# STM32.net
KiCad netlist of a schematic drawn in Altium Designer
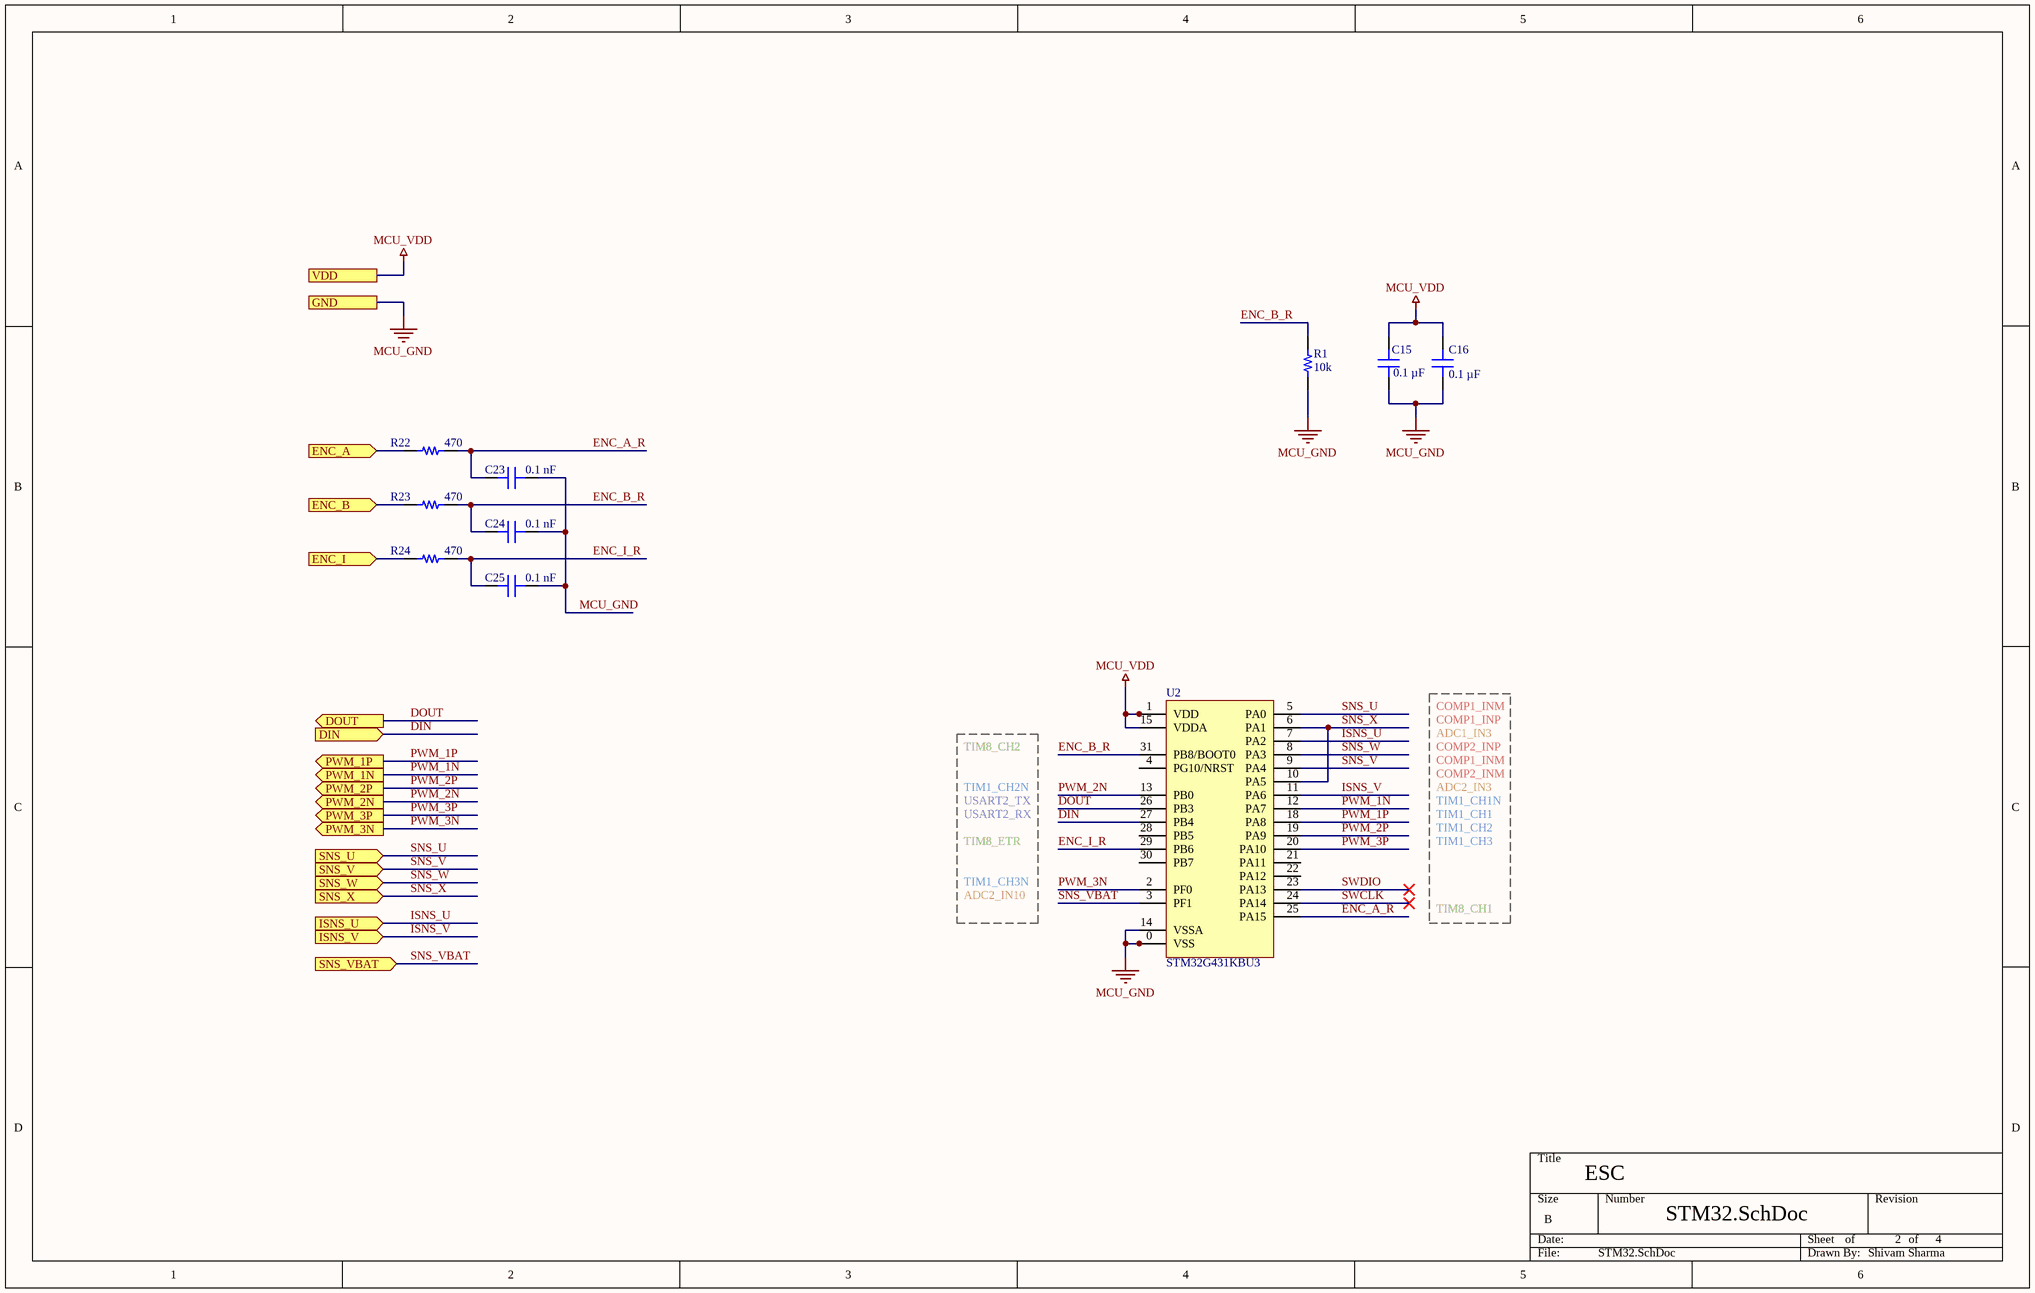
[diagram p0: STM32.SchDoc]

(export (version "E")
  (design (tool "Eeschema 10.0.6"))
  (components
    (comp (ref "C15")
      (value "0.1 µF")
      (footprint "CAP 0402_1005")
      (description "CAP CER 0.1UF 16V X7R 0402")
      (fields (field (name "PART NUMBER") "C0402C104K4RACAUTO") (field (name "MANUFACTURER") "KEMET"))
      (libsource (lib "Celestial Altium Library - altium_library") (part "Capacitor"))
    )
    (comp (ref "C16")
      (value "0.1 µF")
      (footprint "CAP 0402_1005")
      (description "CAP CER 0.1UF 16V X7R 0402")
      (fields (field (name "PART NUMBER") "C0402C104K4RACAUTO") (field (name "MANUFACTURER") "KEMET"))
      (libsource (lib "Celestial Altium Library - altium_library") (part "Capacitor"))
    )
    (comp (ref "C23")
      (value "0.1 nF")
      (footprint "CAP 0402_1005")
      (description "CAP CER 0.1UF 16V X7R 0402")
      (fields (field (name "PART NUMBER") "C0402C104K4RACAUTO") (field (name "MANUFACTURER") "KEMET"))
      (libsource (lib "Celestial Altium Library - altium_library") (part "Capacitor"))
    )
    (comp (ref "C24")
      (value "0.1 nF")
      (footprint "CAP 0402_1005")
      (description "CAP CER 0.1UF 16V X7R 0402")
      (fields (field (name "PART NUMBER") "C0402C104K4RACAUTO") (field (name "MANUFACTURER") "KEMET"))
      (libsource (lib "Celestial Altium Library - altium_library") (part "Capacitor"))
    )
    (comp (ref "C25")
      (value "0.1 nF")
      (footprint "CAP 0402_1005")
      (description "CAP CER 0.1UF 16V X7R 0402")
      (fields (field (name "PART NUMBER") "C0402C104K4RACAUTO") (field (name "MANUFACTURER") "KEMET"))
      (libsource (lib "Celestial Altium Library - altium_library") (part "Capacitor"))
    )
    (comp (ref "R1")
      (value "10k")
      (footprint "RES 0402_1005")
      (description "RES 14.3K OHM 1% 1/10W 0402")
      (fields
        (field (name "PART NUMBER") "RK73H1ETTP1432F")
        (field (name "MANUFACTURER") "KOA Speer Electronics, Inc.")
      )
      (libsource (lib "Celestial Altium Library - altium_library") (part "Resistor"))
    )
    (comp (ref "R22")
      (value "470")
      (footprint "RES 0402_1005")
      (description "RES 14.3K OHM 1% 1/10W 0402")
      (fields
        (field (name "PART NUMBER") "RK73H1ETTP1432F")
        (field (name "MANUFACTURER") "KOA Speer Electronics, Inc.")
      )
      (libsource (lib "Celestial Altium Library - altium_library") (part "Resistor"))
    )
    (comp (ref "R23")
      (value "470")
      (footprint "RES 0402_1005")
      (description "RES 14.3K OHM 1% 1/10W 0402")
      (fields
        (field (name "PART NUMBER") "RK73H1ETTP1432F")
        (field (name "MANUFACTURER") "KOA Speer Electronics, Inc.")
      )
      (libsource (lib "Celestial Altium Library - altium_library") (part "Resistor"))
    )
    (comp (ref "R24")
      (value "470")
      (footprint "RES 0402_1005")
      (description "RES 14.3K OHM 1% 1/10W 0402")
      (fields
        (field (name "PART NUMBER") "RK73H1ETTP1432F")
        (field (name "MANUFACTURER") "KOA Speer Electronics, Inc.")
      )
      (libsource (lib "Celestial Altium Library - altium_library") (part "Resistor"))
    )
    (comp (ref "U2")
      (value "STM32G431KBU3")
      (footprint "QFN50P400X400X60-32N")
      (description "MCU UFQFPN-32")
      (libsource (lib "IC") (part "STM32G431KBU3"))
    )
  )
  (nets
    (net (code "1") (name "/DIN") (class "Default")
      (node (ref "U2") (pin "27") (pinfunction "PB4_27") (pintype "passive"))
    )
    (net (code "2") (name "/DOUT") (class "Default")
      (node (ref "U2") (pin "26") (pinfunction "PB3_26") (pintype "passive"))
    )
    (net (code "3") (name "/ENC_A") (class "Default")
      (node (ref "R22") (pin "1") (pinfunction "1_1") (pintype "passive"))
    )
    (net (code "4") (name "/ENC_A_R") (class "Default")
      (node (ref "C23") (pin "1") (pinfunction "1_1") (pintype "passive"))
      (node (ref "R22") (pin "2") (pinfunction "2_2") (pintype "passive"))
      (node (ref "U2") (pin "25") (pinfunction "PA15_25") (pintype "passive"))
    )
    (net (code "5") (name "/ENC_B") (class "Default")
      (node (ref "R23") (pin "1") (pinfunction "1_1") (pintype "passive"))
    )
    (net (code "6") (name "/ENC_B_R") (class "Default")
      (node (ref "C24") (pin "1") (pinfunction "1_1") (pintype "passive"))
      (node (ref "R1") (pin "2") (pinfunction "2_2") (pintype "passive"))
      (node (ref "R23") (pin "2") (pinfunction "2_2") (pintype "passive"))
      (node (ref "U2") (pin "31") (pinfunction "PB8/BOOT0_31") (pintype "passive"))
    )
    (net (code "7") (name "/ENC_I") (class "Default")
      (node (ref "R24") (pin "1") (pinfunction "1_1") (pintype "passive"))
    )
    (net (code "8") (name "/ENC_I_R") (class "Default")
      (node (ref "C25") (pin "1") (pinfunction "1_1") (pintype "passive"))
      (node (ref "R24") (pin "2") (pinfunction "2_2") (pintype "passive"))
      (node (ref "U2") (pin "29") (pinfunction "PB6_29") (pintype "passive"))
    )
    (net (code "9") (name "/ISNS_U") (class "Default")
      (node (ref "U2") (pin "7") (pinfunction "PA2_7") (pintype "passive"))
    )
    (net (code "10") (name "/ISNS_V") (class "Default")
      (node (ref "U2") (pin "11") (pinfunction "PA6_11") (pintype "passive"))
    )
    (net (code "11") (name "/PWM_1N") (class "Default")
      (node (ref "U2") (pin "12") (pinfunction "PA7_12") (pintype "passive"))
    )
    (net (code "12") (name "/PWM_1P") (class "Default")
      (node (ref "U2") (pin "18") (pinfunction "PA8_18") (pintype "passive"))
    )
    (net (code "13") (name "/PWM_2N") (class "Default")
      (node (ref "U2") (pin "13") (pinfunction "PB0_13") (pintype "passive"))
    )
    (net (code "14") (name "/PWM_2P") (class "Default")
      (node (ref "U2") (pin "19") (pinfunction "PA9_19") (pintype "passive"))
    )
    (net (code "15") (name "/PWM_3N") (class "Default")
      (node (ref "U2") (pin "2") (pinfunction "PF0_2") (pintype "passive"))
    )
    (net (code "16") (name "/PWM_3P") (class "Default")
      (node (ref "U2") (pin "20") (pinfunction "PA10_20") (pintype "passive"))
    )
    (net (code "17") (name "/SNS_U") (class "Default")
      (node (ref "U2") (pin "5") (pinfunction "PA0_5") (pintype "passive"))
    )
    (net (code "18") (name "/SNS_V") (class "Default")
      (node (ref "U2") (pin "9") (pinfunction "PA4_9") (pintype "passive"))
    )
    (net (code "19") (name "/SNS_VBAT") (class "Default")
      (node (ref "U2") (pin "3") (pinfunction "PF1_3") (pintype "passive"))
    )
    (net (code "20") (name "/SNS_W") (class "Default")
      (node (ref "U2") (pin "8") (pinfunction "PA3_8") (pintype "passive"))
    )
    (net (code "21") (name "/SNS_X") (class "Default")
      (node (ref "U2") (pin "10") (pinfunction "PA5_10") (pintype "passive"))
      (node (ref "U2") (pin "6") (pinfunction "PA1_6") (pintype "passive"))
    )
    (net (code "22") (name "/SWCLK") (class "Default")
      (node (ref "U2") (pin "24") (pinfunction "PA14_24") (pintype "passive+no_connect"))
    )
    (net (code "23") (name "/SWDIO") (class "Default")
      (node (ref "U2") (pin "23") (pinfunction "PA13_23") (pintype "passive+no_connect"))
    )
    (net (code "24") (name "MCU_GND") (class "Default")
      (node (ref "C15") (pin "1") (pinfunction "1_1") (pintype "passive"))
      (node (ref "C16") (pin "1") (pinfunction "1_1") (pintype "passive"))
      (node (ref "C23") (pin "2") (pinfunction "2_2") (pintype "passive"))
      (node (ref "C24") (pin "2") (pinfunction "2_2") (pintype "passive"))
      (node (ref "C25") (pin "2") (pinfunction "2_2") (pintype "passive"))
      (node (ref "R1") (pin "1") (pinfunction "1_1") (pintype "passive"))
      (node (ref "U2") (pin "0") (pinfunction "VSS_0") (pintype "passive"))
      (node (ref "U2") (pin "14") (pinfunction "VSSA_14") (pintype "passive"))
      (node (ref "U2") (pin "16") (pinfunction "VSS_16") (pintype "passive"))
      (node (ref "U2") (pin "32") (pinfunction "VSS_32") (pintype "passive"))
    )
    (net (code "25") (name "MCU_VDD") (class "Default")
      (node (ref "C15") (pin "2") (pinfunction "2_2") (pintype "passive"))
      (node (ref "C16") (pin "2") (pinfunction "2_2") (pintype "passive"))
      (node (ref "U2") (pin "1") (pinfunction "VDD_1") (pintype "passive"))
      (node (ref "U2") (pin "15") (pinfunction "VDDA_15") (pintype "passive"))
      (node (ref "U2") (pin "17") (pinfunction "VDD_17") (pintype "passive"))
    )
    (net (code "26") (name "unconnected-(U2-PA11-Pad21)") (class "Default")
      (node (ref "U2") (pin "21") (pinfunction "PA11_21") (pintype "passive"))
    )
    (net (code "27") (name "unconnected-(U2-PA12-Pad22)") (class "Default")
      (node (ref "U2") (pin "22") (pinfunction "PA12_22") (pintype "passive"))
    )
    (net (code "28") (name "unconnected-(U2-PB5-Pad28)") (class "Default")
      (node (ref "U2") (pin "28") (pinfunction "PB5_28") (pintype "passive"))
    )
    (net (code "29") (name "unconnected-(U2-PB7-Pad30)") (class "Default")
      (node (ref "U2") (pin "30") (pinfunction "PB7_30") (pintype "passive"))
    )
    (net (code "30") (name "unconnected-(U2-PG10{slash}NRST-Pad4)") (class "Default")
      (node (ref "U2") (pin "4") (pinfunction "PG10/NRST_4") (pintype "passive"))
    )
  )
)
